# Sche_Voltage_regulator.net
KiCad netlist of a schematic drawn in Altium Designer
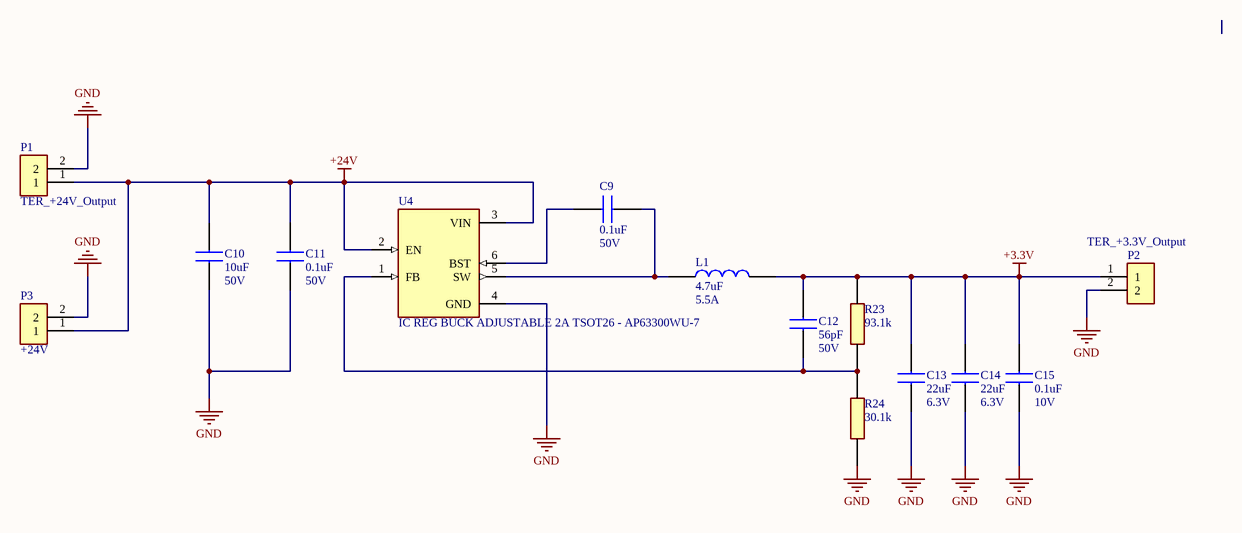
[diagram p0: Sche_Voltage regulator.SchDoc]

(export (version "E")
  (design (tool "Eeschema 10.0.6"))
  (components
    (comp (ref "C9")
      (value "0.1uF")
      (footprint "C 0603")
      (description "CAP CER 0.1UF 50V X7R 0603")
      (fields (field (name "ALTIUM_UNNAMED_1") "50V"))
      (libsource (lib "LAB_COATING COF_MACHINE") (part "CAP CER 0.1UF 50V X7R 0603 - ESD35C104K4T2A-24"))
    )
    (comp (ref "C10")
      (value "10uF")
      (footprint "CAPC3225X290N")
      (description "CAP CER 10UF 50V Y5V 1210")
      (fields
        (field (name "MANUFACTURER_PART_NUMBER") "12105G106ZAT2A/500")
        (field (name "ALTIUM_UNNAMED_1") "50V")
      )
      (libsource (lib "LAB_COATING COF_MACHINE") (part "CAP CER 10UF 50V Y5V 1210 - 12105G106ZAT2A"))
    )
    (comp (ref "C11")
      (value "0.1uF")
      (footprint "C 0603")
      (description "CAP CER 0.1UF 50V X7R 0603")
      (fields (field (name "ALTIUM_UNNAMED_1") "50V"))
      (libsource (lib "LAB_COATING COF_MACHINE") (part "CAP CER 0.1UF 50V X7R 0603 - ESD35C104K4T2A-24"))
    )
    (comp (ref "C12")
      (value "56pF")
      (footprint "CAPC1005X55N")
      (description "CAP CER 56PF 50V C0G/NPO 0402")
      (fields
        (field (name "ALTIUM_UNNAMED_1") "50V")
        (field (name "MANUFACTURER_PART_NUMBER") "CC0402JRNPO9BN560")
      )
      (libsource (lib "LAB_COATING COF_MACHINE") (part "CAP CER 56PF 50V C0G/NPO 0402 - CC0402JRNPO9BN560"))
    )
    (comp (ref "C13")
      (value "22uF")
      (footprint "PCB_COF_1.2:C 0603")
      (description "CAP CER 22UF 6.3V X5R 0603")
      (fields (field (name "ALTIUM_UNNAMED_1") "6.3V"))
      (libsource (lib "LAB_COATING COF_MACHINE") (part "CAP CER 22UF 6.3V X5R 0603 - GRM188R60J226MEA0D"))
    )
    (comp (ref "C14")
      (value "22uF")
      (footprint "PCB_COF_1.2:C 0603")
      (description "CAP CER 22UF 6.3V X5R 0603")
      (fields (field (name "ALTIUM_UNNAMED_1") "6.3V"))
      (libsource (lib "LAB_COATING COF_MACHINE") (part "CAP CER 22UF 6.3V X5R 0603 - GRM188R60J226MEA0D"))
    )
    (comp (ref "C15")
      (value "0.1uF")
      (footprint "CAPC1608X95N")
      (description "Multilayer Ceramic Capacitors MLCC - SMD/SMT")
      (fields
        (field (name "ALTIUM_UNNAMED_1") "10V")
        (field (name "MANUFACTURER_PART_NUMBER") "C0603C104K8RACTU/1K")
      )
      (libsource (lib "LAB_COATING COF_MACHINE") (part "CAP CER 0.1UF 10V X7R 0603 - C0603C104K8RACTU"))
    )
    (comp (ref "L1")
      (value "4.7uF")
      (footprint "INDM6965X300N")
      (description "FIXED IND 4.7UH 5.5A 40 MOHM SMD")
      (fields
        (field (name "MANUFACTURER_PART_NUMBER") "IHLP2525CZER4R7M01")
        (field (name "MOUSER PART NUMBER") "70-IHLP2525CZER4R7M1")
        (field (name "ALTIUM_UNNAMED_1") "5.5A")
      )
      (libsource (lib "LAB_COATING COF_MACHINE") (part "IND 4.7UH 5.5A 40 MOHM SMD - IHLP2525CZER4R7M01"))
    )
    (comp (ref "P1")
      (value "TERM BLK 2P SIDE ENT 5.08MM PCB - 282837-2")
      (footprint "TE_282837-2")
      (description "TERM BLK 2P SIDE ENT 5.08MM PCB")
      (fields
        (field (name "MP") "282837-2")
        (field (name "MF") "TE Connectivity")
        (field (name "COMMENT_1") "TER_+24V_Output")
      )
      (libsource (lib "LAB_COATING COF_MACHINE") (part "TERM BLK 2P SIDE ENT 5.08MM PCB - 282837-2"))
    )
    (comp (ref "P2")
      (value "282837-2")
      (footprint "TE_282837-2")
      (description "Connector Terminal Blocks Receptacle 2 Position 5.08mm Solder Straight Thru-Hole 13.5A/Contact")
      (fields (field (name "MF") "TE Connectivity") (field (name "COMMENT_1") "TER_+3.3V_Output"))
      (libsource (lib "") (part "282837-2_1"))
    )
    (comp (ref "P3")
      (value "282837-2")
      (footprint "TE_282837-2")
      (description "Connector Terminal Blocks Receptacle 2 Position 5.08mm Solder Straight Thru-Hole 13.5A/Contact")
      (fields (field (name "MF") "TE Connectivity") (field (name "COMMENT_1") "+24V"))
      (libsource (lib "Con_TerminalBlock_2Pin_5.08mm") (part "282837-2"))
    )
    (comp (ref "R23")
      (value "93.1k")
      (footprint "RESC1005X40N")
      (description "RES 93.1K OHM 1% 1/16W 0402")
      (fields
        (field (name "MANUFACTURER_PART_NUMBER") "RC0402FR-0793K1L")
        (field (name "MOUSER PART NUMBER") "603-RC0402FR-0793K1L")
      )
      (libsource (lib "LAB_COATING COF_MACHINE") (part "RES 93.1K OHM 1% 1/16W 0402 - RC0402FR-0793K1L"))
    )
    (comp (ref "R24")
      (value "30.1k")
      (footprint "ERJ2RKD1004X")
      (description "RES SMD 30.1K OHM 1% 1/10W 0402")
      (fields
        (field (name "MANUFACTURER_PART_NUMBER") "ERJ-2RKF3012X")
        (field (name "MOUSER PART NUMBER") "667-ERJ-2RKF3012X")
      )
      (libsource (lib "LAB_COATING COF_MACHINE") (part "RES SMD 30.1K OHM 1% 1/10W 0402 - ERJ-2RKF3012X"))
    )
    (comp (ref "U4")
      (value "IC REG BUCK ADJUSTABLE 2A TSOT26 - AP63300WU-7")
      (footprint "VOLT_REGULATOR_AP63300WU-7:SOT95P280X100-6N")
      (description "IC REG BUCK ADJUSTABLE 2A TSOT26")
      (fields (field (name "MP") "AP63300WU-7") (field (name "MF") "Diodes Incorporated"))
      (libsource (lib "LAB_COATING COF_MACHINE") (part "IC REG BUCK ADJUSTABLE 2A TSOT26 - AP63300WU-7"))
    )
  )
  (nets
    (net (code "1") (name "+3.3V") (class "Default")
      (node (ref "C12") (pin "2") (pinfunction "2_2") (pintype "passive"))
      (node (ref "C13") (pin "2") (pinfunction "2_2") (pintype "passive"))
      (node (ref "C14") (pin "2") (pinfunction "2_2") (pintype "passive"))
      (node (ref "C15") (pin "2") (pinfunction "2_2") (pintype "passive"))
      (node (ref "L1") (pin "2") (pinfunction "2_2") (pintype "passive"))
      (node (ref "P2") (pin "1") (pinfunction "1_1") (pintype "passive"))
      (node (ref "R23") (pin "2") (pinfunction "2_2") (pintype "passive"))
    )
    (net (code "2") (name "+24V") (class "Default")
      (node (ref "C10") (pin "2") (pinfunction "2_2") (pintype "passive"))
      (node (ref "C11") (pin "2") (pinfunction "2_2") (pintype "passive"))
      (node (ref "P1") (pin "1") (pinfunction "1_1") (pintype "passive"))
      (node (ref "P3") (pin "1") (pinfunction "1_1") (pintype "passive"))
      (node (ref "U4") (pin "2") (pinfunction "EN_2") (pintype "input"))
      (node (ref "U4") (pin "3") (pinfunction "VIN_3") (pintype "power_in"))
    )
    (net (code "3") (name "GND") (class "Default")
      (node (ref "C10") (pin "1") (pinfunction "1_1") (pintype "passive"))
      (node (ref "C11") (pin "1") (pinfunction "1_1") (pintype "passive"))
      (node (ref "C13") (pin "1") (pinfunction "1_1") (pintype "passive"))
      (node (ref "C14") (pin "1") (pinfunction "1_1") (pintype "passive"))
      (node (ref "C15") (pin "1") (pinfunction "1_1") (pintype "passive"))
      (node (ref "P1") (pin "2") (pinfunction "2_2") (pintype "passive"))
      (node (ref "P2") (pin "2") (pinfunction "2_2") (pintype "passive"))
      (node (ref "P3") (pin "2") (pinfunction "2_2") (pintype "passive"))
      (node (ref "R24") (pin "1") (pinfunction "1_1") (pintype "passive"))
      (node (ref "U4") (pin "4") (pinfunction "GND_4") (pintype "power_in"))
    )
    (net (code "4") (name "Net-(U4-BST)") (class "Default")
      (node (ref "C9") (pin "1") (pinfunction "1_1") (pintype "passive"))
      (node (ref "U4") (pin "6") (pinfunction "BST_6") (pintype "input"))
    )
    (net (code "5") (name "Net-(U4-FB)") (class "Default")
      (node (ref "C12") (pin "1") (pinfunction "1_1") (pintype "passive"))
      (node (ref "R23") (pin "1") (pinfunction "1_1") (pintype "passive"))
      (node (ref "R24") (pin "2") (pinfunction "2_2") (pintype "passive"))
      (node (ref "U4") (pin "1") (pinfunction "FB_1") (pintype "input"))
    )
    (net (code "6") (name "Net-(U4-SW)") (class "Default")
      (node (ref "C9") (pin "2") (pinfunction "2_2") (pintype "passive"))
      (node (ref "L1") (pin "1") (pinfunction "1_1") (pintype "passive"))
      (node (ref "U4") (pin "5") (pinfunction "SW_5") (pintype "output"))
    )
  )
)
